# MC21R01_uC_Power.net
KiCad netlist of a schematic drawn in Altium Designer
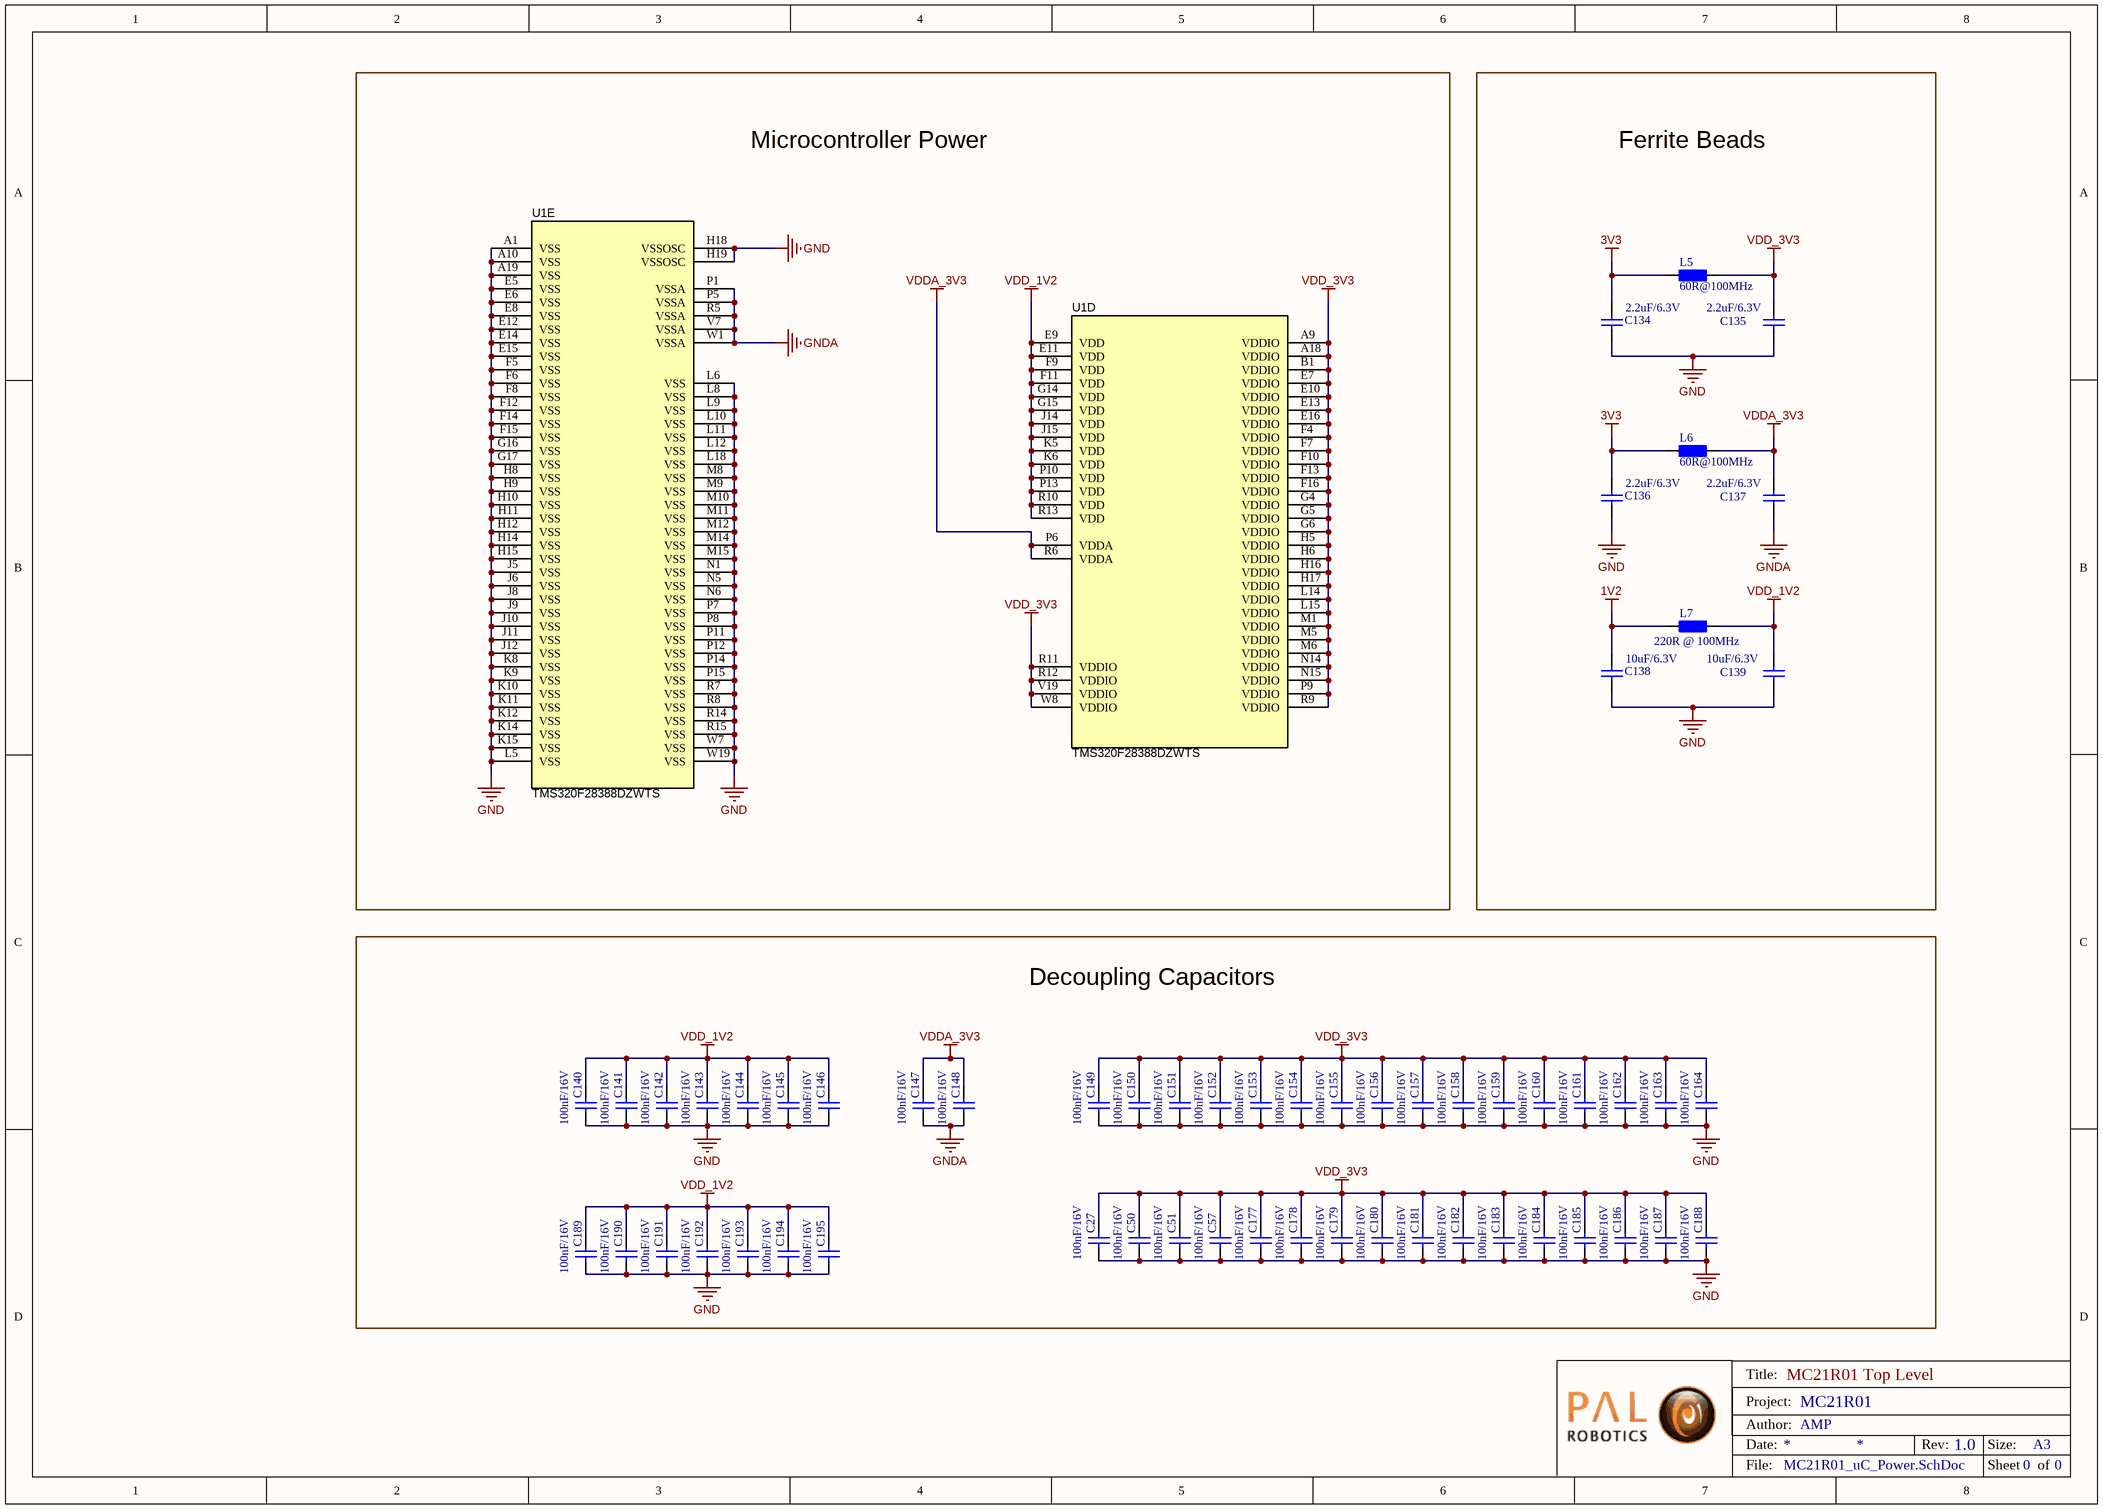
[diagram p0: MC21R01_uC_Power.SchDoc]

(export (version "E")
  (design (tool "Eeschema 10.0.6"))
  (components
    (comp (ref "C27")
      (value "100nF/16V")
      (footprint "PAL_Capacitors:0402 SMD Capacitor")
      (description "100nF/16V 0402 10% Tolerance X7R Multilayer Ceramic Chip Capacitor")
      (fields (field (name "Comment") "100nF/16V 0402 10% X7R"))
      (libsource (lib "PAL_Capacitors") (part "100nF/16V 0402 10% X7R"))
    )
    (comp (ref "C50")
      (value "100nF/16V")
      (footprint "PAL_Capacitors:0402 SMD Capacitor")
      (description "100nF/16V 0402 10% Tolerance X7R Multilayer Ceramic Chip Capacitor")
      (fields (field (name "Comment") "100nF/16V 0402 10% X7R"))
      (libsource (lib "PAL_Capacitors") (part "100nF/16V 0402 10% X7R"))
    )
    (comp (ref "C51")
      (value "100nF/16V")
      (footprint "PAL_Capacitors:0402 SMD Capacitor")
      (description "100nF/16V 0402 10% Tolerance X7R Multilayer Ceramic Chip Capacitor")
      (fields (field (name "Comment") "100nF/16V 0402 10% X7R"))
      (libsource (lib "PAL_Capacitors") (part "100nF/16V 0402 10% X7R"))
    )
    (comp (ref "C57")
      (value "100nF/16V")
      (footprint "PAL_Capacitors:0402 SMD Capacitor")
      (description "100nF/16V 0402 10% Tolerance X7R Multilayer Ceramic Chip Capacitor")
      (fields (field (name "Comment") "100nF/16V 0402 10% X7R"))
      (libsource (lib "PAL_Capacitors") (part "100nF/16V 0402 10% X7R"))
    )
    (comp (ref "C134")
      (value "2.2uF/6.3V")
      (footprint "PAL_Capacitors:0402 SMD Capacitor")
      (description "2.2uF/6.3V 0402 10% Tolerance X5R Multilayer Ceramic Chip Capacitor")
      (fields (field (name "Comment") "2.2uF/6.3V 0402 10% X5R"))
      (libsource (lib "PAL_Capacitors") (part "2.2uF/6.3V 0402 10% X5R_1"))
    )
    (comp (ref "C135")
      (value "2.2uF/6.3V")
      (footprint "PAL_Capacitors:0402 SMD Capacitor")
      (description "2.2uF/6.3V 0402 10% Tolerance X5R Multilayer Ceramic Chip Capacitor")
      (fields (field (name "Comment") "2.2uF/6.3V 0402 10% X5R"))
      (libsource (lib "PAL_Capacitors") (part "2.2uF/6.3V 0402 10% X5R_1"))
    )
    (comp (ref "C136")
      (value "2.2uF/6.3V")
      (footprint "PAL_Capacitors:0402 SMD Capacitor")
      (description "2.2uF/6.3V 0402 10% Tolerance X5R Multilayer Ceramic Chip Capacitor")
      (fields (field (name "Comment") "2.2uF/6.3V 0402 10% X5R"))
      (libsource (lib "PAL_Capacitors") (part "2.2uF/6.3V 0402 10% X5R_1"))
    )
    (comp (ref "C137")
      (value "2.2uF/6.3V")
      (footprint "PAL_Capacitors:0402 SMD Capacitor")
      (description "2.2uF/6.3V 0402 10% Tolerance X5R Multilayer Ceramic Chip Capacitor")
      (fields (field (name "Comment") "2.2uF/6.3V 0402 10% X5R"))
      (libsource (lib "PAL_Capacitors") (part "2.2uF/6.3V 0402 10% X5R_1"))
    )
    (comp (ref "C138")
      (value "10uF/6.3V")
      (footprint "PAL_Capacitors:0402 SMD Capacitor")
      (description "10uF/6.3V 0402 20% Tolerance X5R Multilayer Ceramic Chip Capacitor")
      (fields (field (name "Comment") "10uF/6.3V 0402 20% X5R"))
      (libsource (lib "PAL_Capacitors") (part "10uF/6.3V 0402 20% X5R"))
    )
    (comp (ref "C139")
      (value "10uF/6.3V")
      (footprint "PAL_Capacitors:0402 SMD Capacitor")
      (description "10uF/6.3V 0402 20% Tolerance X5R Multilayer Ceramic Chip Capacitor")
      (fields (field (name "Comment") "10uF/6.3V 0402 20% X5R"))
      (libsource (lib "PAL_Capacitors") (part "10uF/6.3V 0402 20% X5R"))
    )
    (comp (ref "C140")
      (value "100nF/16V")
      (footprint "PAL_Capacitors:0402 SMD Capacitor")
      (description "100nF/16V 0402 10% Tolerance X7R Multilayer Ceramic Chip Capacitor")
      (fields (field (name "Comment") "100nF/16V 0402 10% X7R"))
      (libsource (lib "PAL_Capacitors") (part "100nF/16V 0402 10% X7R"))
    )
    (comp (ref "C141")
      (value "100nF/16V")
      (footprint "PAL_Capacitors:0402 SMD Capacitor")
      (description "100nF/16V 0402 10% Tolerance X7R Multilayer Ceramic Chip Capacitor")
      (fields (field (name "Comment") "100nF/16V 0402 10% X7R"))
      (libsource (lib "PAL_Capacitors") (part "100nF/16V 0402 10% X7R"))
    )
    (comp (ref "C142")
      (value "100nF/16V")
      (footprint "PAL_Capacitors:0402 SMD Capacitor")
      (description "100nF/16V 0402 10% Tolerance X7R Multilayer Ceramic Chip Capacitor")
      (fields (field (name "Comment") "100nF/16V 0402 10% X7R"))
      (libsource (lib "PAL_Capacitors") (part "100nF/16V 0402 10% X7R"))
    )
    (comp (ref "C143")
      (value "100nF/16V")
      (footprint "PAL_Capacitors:0402 SMD Capacitor")
      (description "100nF/16V 0402 10% Tolerance X7R Multilayer Ceramic Chip Capacitor")
      (fields (field (name "Comment") "100nF/16V 0402 10% X7R"))
      (libsource (lib "PAL_Capacitors") (part "100nF/16V 0402 10% X7R"))
    )
    (comp (ref "C144")
      (value "100nF/16V")
      (footprint "PAL_Capacitors:0402 SMD Capacitor")
      (description "100nF/16V 0402 10% Tolerance X7R Multilayer Ceramic Chip Capacitor")
      (fields (field (name "Comment") "100nF/16V 0402 10% X7R"))
      (libsource (lib "PAL_Capacitors") (part "100nF/16V 0402 10% X7R"))
    )
    (comp (ref "C145")
      (value "100nF/16V")
      (footprint "PAL_Capacitors:0402 SMD Capacitor")
      (description "100nF/16V 0402 10% Tolerance X7R Multilayer Ceramic Chip Capacitor")
      (fields (field (name "Comment") "100nF/16V 0402 10% X7R"))
      (libsource (lib "PAL_Capacitors") (part "100nF/16V 0402 10% X7R"))
    )
    (comp (ref "C146")
      (value "100nF/16V")
      (footprint "PAL_Capacitors:0402 SMD Capacitor")
      (description "100nF/16V 0402 10% Tolerance X7R Multilayer Ceramic Chip Capacitor")
      (fields (field (name "Comment") "100nF/16V 0402 10% X7R"))
      (libsource (lib "PAL_Capacitors") (part "100nF/16V 0402 10% X7R"))
    )
    (comp (ref "C147")
      (value "100nF/16V")
      (footprint "PAL_Capacitors:0402 SMD Capacitor")
      (description "100nF/16V 0402 10% Tolerance X7R Multilayer Ceramic Chip Capacitor")
      (fields (field (name "Comment") "100nF/16V 0402 10% X7R"))
      (libsource (lib "PAL_Capacitors") (part "100nF/16V 0402 10% X7R"))
    )
    (comp (ref "C148")
      (value "100nF/16V")
      (footprint "PAL_Capacitors:0402 SMD Capacitor")
      (description "100nF/16V 0402 10% Tolerance X7R Multilayer Ceramic Chip Capacitor")
      (fields (field (name "Comment") "100nF/16V 0402 10% X7R"))
      (libsource (lib "PAL_Capacitors") (part "100nF/16V 0402 10% X7R"))
    )
    (comp (ref "C149")
      (value "100nF/16V")
      (footprint "PAL_Capacitors:0402 SMD Capacitor")
      (description "100nF/16V 0402 10% Tolerance X7R Multilayer Ceramic Chip Capacitor")
      (fields (field (name "Comment") "100nF/16V 0402 10% X7R"))
      (libsource (lib "PAL_Capacitors") (part "100nF/16V 0402 10% X7R"))
    )
    (comp (ref "C150")
      (value "100nF/16V")
      (footprint "PAL_Capacitors:0402 SMD Capacitor")
      (description "100nF/16V 0402 10% Tolerance X7R Multilayer Ceramic Chip Capacitor")
      (fields (field (name "Comment") "100nF/16V 0402 10% X7R"))
      (libsource (lib "PAL_Capacitors") (part "100nF/16V 0402 10% X7R"))
    )
    (comp (ref "C151")
      (value "100nF/16V")
      (footprint "PAL_Capacitors:0402 SMD Capacitor")
      (description "100nF/16V 0402 10% Tolerance X7R Multilayer Ceramic Chip Capacitor")
      (fields (field (name "Comment") "100nF/16V 0402 10% X7R"))
      (libsource (lib "PAL_Capacitors") (part "100nF/16V 0402 10% X7R"))
    )
    (comp (ref "C152")
      (value "100nF/16V")
      (footprint "PAL_Capacitors:0402 SMD Capacitor")
      (description "100nF/16V 0402 10% Tolerance X7R Multilayer Ceramic Chip Capacitor")
      (fields (field (name "Comment") "100nF/16V 0402 10% X7R"))
      (libsource (lib "PAL_Capacitors") (part "100nF/16V 0402 10% X7R"))
    )
    (comp (ref "C153")
      (value "100nF/16V")
      (footprint "PAL_Capacitors:0402 SMD Capacitor")
      (description "100nF/16V 0402 10% Tolerance X7R Multilayer Ceramic Chip Capacitor")
      (fields (field (name "Comment") "100nF/16V 0402 10% X7R"))
      (libsource (lib "PAL_Capacitors") (part "100nF/16V 0402 10% X7R"))
    )
    (comp (ref "C154")
      (value "100nF/16V")
      (footprint "PAL_Capacitors:0402 SMD Capacitor")
      (description "100nF/16V 0402 10% Tolerance X7R Multilayer Ceramic Chip Capacitor")
      (fields (field (name "Comment") "100nF/16V 0402 10% X7R"))
      (libsource (lib "PAL_Capacitors") (part "100nF/16V 0402 10% X7R"))
    )
    (comp (ref "C155")
      (value "100nF/16V")
      (footprint "PAL_Capacitors:0402 SMD Capacitor")
      (description "100nF/16V 0402 10% Tolerance X7R Multilayer Ceramic Chip Capacitor")
      (fields (field (name "Comment") "100nF/16V 0402 10% X7R"))
      (libsource (lib "PAL_Capacitors") (part "100nF/16V 0402 10% X7R"))
    )
    (comp (ref "C156")
      (value "100nF/16V")
      (footprint "PAL_Capacitors:0402 SMD Capacitor")
      (description "100nF/16V 0402 10% Tolerance X7R Multilayer Ceramic Chip Capacitor")
      (fields (field (name "Comment") "100nF/16V 0402 10% X7R"))
      (libsource (lib "PAL_Capacitors") (part "100nF/16V 0402 10% X7R"))
    )
    (comp (ref "C157")
      (value "100nF/16V")
      (footprint "PAL_Capacitors:0402 SMD Capacitor")
      (description "100nF/16V 0402 10% Tolerance X7R Multilayer Ceramic Chip Capacitor")
      (fields (field (name "Comment") "100nF/16V 0402 10% X7R"))
      (libsource (lib "PAL_Capacitors") (part "100nF/16V 0402 10% X7R"))
    )
    (comp (ref "C158")
      (value "100nF/16V")
      (footprint "PAL_Capacitors:0402 SMD Capacitor")
      (description "100nF/16V 0402 10% Tolerance X7R Multilayer Ceramic Chip Capacitor")
      (fields (field (name "Comment") "100nF/16V 0402 10% X7R"))
      (libsource (lib "PAL_Capacitors") (part "100nF/16V 0402 10% X7R"))
    )
    (comp (ref "C159")
      (value "100nF/16V")
      (footprint "PAL_Capacitors:0402 SMD Capacitor")
      (description "100nF/16V 0402 10% Tolerance X7R Multilayer Ceramic Chip Capacitor")
      (fields (field (name "Comment") "100nF/16V 0402 10% X7R"))
      (libsource (lib "PAL_Capacitors") (part "100nF/16V 0402 10% X7R"))
    )
    (comp (ref "C160")
      (value "100nF/16V")
      (footprint "PAL_Capacitors:0402 SMD Capacitor")
      (description "100nF/16V 0402 10% Tolerance X7R Multilayer Ceramic Chip Capacitor")
      (fields (field (name "Comment") "100nF/16V 0402 10% X7R"))
      (libsource (lib "PAL_Capacitors") (part "100nF/16V 0402 10% X7R"))
    )
    (comp (ref "C161")
      (value "100nF/16V")
      (footprint "PAL_Capacitors:0402 SMD Capacitor")
      (description "100nF/16V 0402 10% Tolerance X7R Multilayer Ceramic Chip Capacitor")
      (fields (field (name "Comment") "100nF/16V 0402 10% X7R"))
      (libsource (lib "PAL_Capacitors") (part "100nF/16V 0402 10% X7R"))
    )
    (comp (ref "C162")
      (value "100nF/16V")
      (footprint "PAL_Capacitors:0402 SMD Capacitor")
      (description "100nF/16V 0402 10% Tolerance X7R Multilayer Ceramic Chip Capacitor")
      (fields (field (name "Comment") "100nF/16V 0402 10% X7R"))
      (libsource (lib "PAL_Capacitors") (part "100nF/16V 0402 10% X7R"))
    )
    (comp (ref "C163")
      (value "100nF/16V")
      (footprint "PAL_Capacitors:0402 SMD Capacitor")
      (description "100nF/16V 0402 10% Tolerance X7R Multilayer Ceramic Chip Capacitor")
      (fields (field (name "Comment") "100nF/16V 0402 10% X7R"))
      (libsource (lib "PAL_Capacitors") (part "100nF/16V 0402 10% X7R"))
    )
    (comp (ref "C164")
      (value "100nF/16V")
      (footprint "PAL_Capacitors:0402 SMD Capacitor")
      (description "100nF/16V 0402 10% Tolerance X7R Multilayer Ceramic Chip Capacitor")
      (fields (field (name "Comment") "100nF/16V 0402 10% X7R"))
      (libsource (lib "PAL_Capacitors") (part "100nF/16V 0402 10% X7R"))
    )
    (comp (ref "C177")
      (value "100nF/16V")
      (footprint "PAL_Capacitors:0402 SMD Capacitor")
      (description "100nF/16V 0402 10% Tolerance X7R Multilayer Ceramic Chip Capacitor")
      (fields (field (name "Comment") "100nF/16V 0402 10% X7R"))
      (libsource (lib "PAL_Capacitors") (part "100nF/16V 0402 10% X7R"))
    )
    (comp (ref "C178")
      (value "100nF/16V")
      (footprint "PAL_Capacitors:0402 SMD Capacitor")
      (description "100nF/16V 0402 10% Tolerance X7R Multilayer Ceramic Chip Capacitor")
      (fields (field (name "Comment") "100nF/16V 0402 10% X7R"))
      (libsource (lib "PAL_Capacitors") (part "100nF/16V 0402 10% X7R"))
    )
    (comp (ref "C179")
      (value "100nF/16V")
      (footprint "PAL_Capacitors:0402 SMD Capacitor")
      (description "100nF/16V 0402 10% Tolerance X7R Multilayer Ceramic Chip Capacitor")
      (fields (field (name "Comment") "100nF/16V 0402 10% X7R"))
      (libsource (lib "PAL_Capacitors") (part "100nF/16V 0402 10% X7R"))
    )
    (comp (ref "C180")
      (value "100nF/16V")
      (footprint "PAL_Capacitors:0402 SMD Capacitor")
      (description "100nF/16V 0402 10% Tolerance X7R Multilayer Ceramic Chip Capacitor")
      (fields (field (name "Comment") "100nF/16V 0402 10% X7R"))
      (libsource (lib "PAL_Capacitors") (part "100nF/16V 0402 10% X7R"))
    )
    (comp (ref "C181")
      (value "100nF/16V")
      (footprint "PAL_Capacitors:0402 SMD Capacitor")
      (description "100nF/16V 0402 10% Tolerance X7R Multilayer Ceramic Chip Capacitor")
      (fields (field (name "Comment") "100nF/16V 0402 10% X7R"))
      (libsource (lib "PAL_Capacitors") (part "100nF/16V 0402 10% X7R"))
    )
    (comp (ref "C182")
      (value "100nF/16V")
      (footprint "PAL_Capacitors:0402 SMD Capacitor")
      (description "100nF/16V 0402 10% Tolerance X7R Multilayer Ceramic Chip Capacitor")
      (fields (field (name "Comment") "100nF/16V 0402 10% X7R"))
      (libsource (lib "PAL_Capacitors") (part "100nF/16V 0402 10% X7R"))
    )
    (comp (ref "C183")
      (value "100nF/16V")
      (footprint "PAL_Capacitors:0402 SMD Capacitor")
      (description "100nF/16V 0402 10% Tolerance X7R Multilayer Ceramic Chip Capacitor")
      (fields (field (name "Comment") "100nF/16V 0402 10% X7R"))
      (libsource (lib "PAL_Capacitors") (part "100nF/16V 0402 10% X7R"))
    )
    (comp (ref "C184")
      (value "100nF/16V")
      (footprint "PAL_Capacitors:0402 SMD Capacitor")
      (description "100nF/16V 0402 10% Tolerance X7R Multilayer Ceramic Chip Capacitor")
      (fields (field (name "Comment") "100nF/16V 0402 10% X7R"))
      (libsource (lib "PAL_Capacitors") (part "100nF/16V 0402 10% X7R"))
    )
    (comp (ref "C185")
      (value "100nF/16V")
      (footprint "PAL_Capacitors:0402 SMD Capacitor")
      (description "100nF/16V 0402 10% Tolerance X7R Multilayer Ceramic Chip Capacitor")
      (fields (field (name "Comment") "100nF/16V 0402 10% X7R"))
      (libsource (lib "PAL_Capacitors") (part "100nF/16V 0402 10% X7R"))
    )
    (comp (ref "C186")
      (value "100nF/16V")
      (footprint "PAL_Capacitors:0402 SMD Capacitor")
      (description "100nF/16V 0402 10% Tolerance X7R Multilayer Ceramic Chip Capacitor")
      (fields (field (name "Comment") "100nF/16V 0402 10% X7R"))
      (libsource (lib "PAL_Capacitors") (part "100nF/16V 0402 10% X7R"))
    )
    (comp (ref "C187")
      (value "100nF/16V")
      (footprint "PAL_Capacitors:0402 SMD Capacitor")
      (description "100nF/16V 0402 10% Tolerance X7R Multilayer Ceramic Chip Capacitor")
      (fields (field (name "Comment") "100nF/16V 0402 10% X7R"))
      (libsource (lib "PAL_Capacitors") (part "100nF/16V 0402 10% X7R"))
    )
    (comp (ref "C188")
      (value "100nF/16V")
      (footprint "PAL_Capacitors:0402 SMD Capacitor")
      (description "100nF/16V 0402 10% Tolerance X7R Multilayer Ceramic Chip Capacitor")
      (fields (field (name "Comment") "100nF/16V 0402 10% X7R"))
      (libsource (lib "PAL_Capacitors") (part "100nF/16V 0402 10% X7R"))
    )
    (comp (ref "C189")
      (value "100nF/16V")
      (footprint "PAL_Capacitors:0402 SMD Capacitor")
      (description "100nF/16V 0402 10% Tolerance X7R Multilayer Ceramic Chip Capacitor")
      (fields (field (name "Comment") "100nF/16V 0402 10% X7R"))
      (libsource (lib "PAL_Capacitors") (part "100nF/16V 0402 10% X7R"))
    )
    (comp (ref "C190")
      (value "100nF/16V")
      (footprint "PAL_Capacitors:0402 SMD Capacitor")
      (description "100nF/16V 0402 10% Tolerance X7R Multilayer Ceramic Chip Capacitor")
      (fields (field (name "Comment") "100nF/16V 0402 10% X7R"))
      (libsource (lib "PAL_Capacitors") (part "100nF/16V 0402 10% X7R"))
    )
    (comp (ref "C191")
      (value "100nF/16V")
      (footprint "PAL_Capacitors:0402 SMD Capacitor")
      (description "100nF/16V 0402 10% Tolerance X7R Multilayer Ceramic Chip Capacitor")
      (fields (field (name "Comment") "100nF/16V 0402 10% X7R"))
      (libsource (lib "PAL_Capacitors") (part "100nF/16V 0402 10% X7R"))
    )
    (comp (ref "C192")
      (value "100nF/16V")
      (footprint "PAL_Capacitors:0402 SMD Capacitor")
      (description "100nF/16V 0402 10% Tolerance X7R Multilayer Ceramic Chip Capacitor")
      (fields (field (name "Comment") "100nF/16V 0402 10% X7R"))
      (libsource (lib "PAL_Capacitors") (part "100nF/16V 0402 10% X7R"))
    )
    (comp (ref "C193")
      (value "100nF/16V")
      (footprint "PAL_Capacitors:0402 SMD Capacitor")
      (description "100nF/16V 0402 10% Tolerance X7R Multilayer Ceramic Chip Capacitor")
      (fields (field (name "Comment") "100nF/16V 0402 10% X7R"))
      (libsource (lib "PAL_Capacitors") (part "100nF/16V 0402 10% X7R"))
    )
    (comp (ref "C194")
      (value "100nF/16V")
      (footprint "PAL_Capacitors:0402 SMD Capacitor")
      (description "100nF/16V 0402 10% Tolerance X7R Multilayer Ceramic Chip Capacitor")
      (fields (field (name "Comment") "100nF/16V 0402 10% X7R"))
      (libsource (lib "PAL_Capacitors") (part "100nF/16V 0402 10% X7R"))
    )
    (comp (ref "C195")
      (value "100nF/16V")
      (footprint "PAL_Capacitors:0402 SMD Capacitor")
      (description "100nF/16V 0402 10% Tolerance X7R Multilayer Ceramic Chip Capacitor")
      (fields (field (name "Comment") "100nF/16V 0402 10% X7R"))
      (libsource (lib "PAL_Capacitors") (part "100nF/16V 0402 10% X7R"))
    )
    (comp (ref "L5")
      (value "60R@100MHz")
      (footprint "PAL_Inductors:0603 SMD inductor")
      (description "Ferrite Bead, 60 ohm, 0603 [1608 Metric], 3 A, 0.04 ohm, ± 25%")
      (fields (field (name "MPN") "742792602") (field (name "MF") "Wurth Electronik"))
      (libsource (lib "PAL_Inductors") (part "FB, 60 ohm, 0603 [1608 Metric], 3 A, 0.04 ohm, ± 25%"))
    )
    (comp (ref "L6")
      (value "60R@100MHz")
      (footprint "PAL_Inductors:0603 SMD inductor")
      (description "Ferrite Bead, 60 ohm, 0603 [1608 Metric], 3 A, 0.04 ohm, ± 25%")
      (fields (field (name "MPN") "742792602") (field (name "MF") "Wurth Electronik"))
      (libsource (lib "PAL_Inductors") (part "FB, 60 ohm, 0603 [1608 Metric], 3 A, 0.04 ohm, ± 25%"))
    )
    (comp (ref "L7")
      (value "220R @ 100MHz")
      (footprint "PAL_Inductors:0603 SMD inductor")
      (description "Ferrite Bead, 220 ohm, 0603 [1608 Metric], 2 A, 0.05 ohm, ± 25%")
      (fields (field (name "MPN") "BLM18EG221SN1D") (field (name "MF") "MURATA"))
      (libsource (lib "PAL_Inductors") (part "FB, 220 ohm, 0603 [1608 Metric], 2 A, 0.05 ohm, ± 25%"))
    )
    (comp (ref "U1")
      (value "TMS320F28388DZWTS")
      (footprint "ZWT0337A")
      (description "TMS320F28388DZWTS, ZWT0337A (NFBGA-337)")
      (fields
        (field (name "MANUFACTURER") "Texas Instruments")
        (field (name "PARTNUMBER") "TMS320F28388DZWTS")
      )
      (libsource (lib "PAL_devices") (part "TMS320F28388"))
    )
  )
  (nets
    (net (code "1") (name "1V2") (class "Default")
      (node (ref "C138") (pin "1") (pinfunction "1_1") (pintype "passive"))
      (node (ref "L7") (pin "2") (pinfunction "2_2") (pintype "passive"))
    )
    (net (code "2") (name "3V3") (class "Default")
      (node (ref "C134") (pin "1") (pinfunction "1_1") (pintype "passive"))
      (node (ref "C136") (pin "1") (pinfunction "1_1") (pintype "passive"))
      (node (ref "L5") (pin "2") (pinfunction "2_2") (pintype "passive"))
      (node (ref "L6") (pin "2") (pinfunction "2_2") (pintype "passive"))
    )
    (net (code "3") (name "GND") (class "Default")
      (node (ref "C134") (pin "2") (pinfunction "2_2") (pintype "passive"))
      (node (ref "C135") (pin "2") (pinfunction "2_2") (pintype "passive"))
      (node (ref "C136") (pin "2") (pinfunction "2_2") (pintype "passive"))
      (node (ref "C138") (pin "2") (pinfunction "2_2") (pintype "passive"))
      (node (ref "C139") (pin "2") (pinfunction "2_2") (pintype "passive"))
      (node (ref "C140") (pin "2") (pinfunction "2_2") (pintype "passive"))
      (node (ref "C141") (pin "2") (pinfunction "2_2") (pintype "passive"))
      (node (ref "C142") (pin "2") (pinfunction "2_2") (pintype "passive"))
      (node (ref "C143") (pin "2") (pinfunction "2_2") (pintype "passive"))
      (node (ref "C144") (pin "2") (pinfunction "2_2") (pintype "passive"))
      (node (ref "C145") (pin "2") (pinfunction "2_2") (pintype "passive"))
      (node (ref "C146") (pin "2") (pinfunction "2_2") (pintype "passive"))
      (node (ref "C149") (pin "2") (pinfunction "2_2") (pintype "passive"))
      (node (ref "C150") (pin "2") (pinfunction "2_2") (pintype "passive"))
      (node (ref "C151") (pin "2") (pinfunction "2_2") (pintype "passive"))
      (node (ref "C152") (pin "2") (pinfunction "2_2") (pintype "passive"))
      (node (ref "C153") (pin "2") (pinfunction "2_2") (pintype "passive"))
      (node (ref "C154") (pin "2") (pinfunction "2_2") (pintype "passive"))
      (node (ref "C155") (pin "2") (pinfunction "2_2") (pintype "passive"))
      (node (ref "C156") (pin "2") (pinfunction "2_2") (pintype "passive"))
      (node (ref "C157") (pin "2") (pinfunction "2_2") (pintype "passive"))
      (node (ref "C158") (pin "2") (pinfunction "2_2") (pintype "passive"))
      (node (ref "C159") (pin "2") (pinfunction "2_2") (pintype "passive"))
      (node (ref "C160") (pin "2") (pinfunction "2_2") (pintype "passive"))
      (node (ref "C161") (pin "2") (pinfunction "2_2") (pintype "passive"))
      (node (ref "C162") (pin "2") (pinfunction "2_2") (pintype "passive"))
      (node (ref "C163") (pin "2") (pinfunction "2_2") (pintype "passive"))
      (node (ref "C164") (pin "2") (pinfunction "2_2") (pintype "passive"))
      (node (ref "C177") (pin "2") (pinfunction "2_2") (pintype "passive"))
      (node (ref "C178") (pin "2") (pinfunction "2_2") (pintype "passive"))
      (node (ref "C179") (pin "2") (pinfunction "2_2") (pintype "passive"))
      (node (ref "C180") (pin "2") (pinfunction "2_2") (pintype "passive"))
      (node (ref "C181") (pin "2") (pinfunction "2_2") (pintype "passive"))
      (node (ref "C182") (pin "2") (pinfunction "2_2") (pintype "passive"))
      (node (ref "C183") (pin "2") (pinfunction "2_2") (pintype "passive"))
      (node (ref "C184") (pin "2") (pinfunction "2_2") (pintype "passive"))
      (node (ref "C185") (pin "2") (pinfunction "2_2") (pintype "passive"))
      (node (ref "C186") (pin "2") (pinfunction "2_2") (pintype "passive"))
      (node (ref "C187") (pin "2") (pinfunction "2_2") (pintype "passive"))
      (node (ref "C188") (pin "2") (pinfunction "2_2") (pintype "passive"))
      (node (ref "C189") (pin "2") (pinfunction "2_2") (pintype "passive"))
      (node (ref "C190") (pin "2") (pinfunction "2_2") (pintype "passive"))
      (node (ref "C191") (pin "2") (pinfunction "2_2") (pintype "passive"))
      (node (ref "C192") (pin "2") (pinfunction "2_2") (pintype "passive"))
      (node (ref "C193") (pin "2") (pinfunction "2_2") (pintype "passive"))
      (node (ref "C194") (pin "2") (pinfunction "2_2") (pintype "passive"))
      (node (ref "C195") (pin "2") (pinfunction "2_2") (pintype "passive"))
      (node (ref "C27") (pin "2") (pinfunction "2_2") (pintype "passive"))
      (node (ref "C50") (pin "2") (pinfunction "2_2") (pintype "passive"))
      (node (ref "C51") (pin "2") (pinfunction "2_2") (pintype "passive"))
      (node (ref "C57") (pin "2") (pinfunction "2_2") (pintype "passive"))
      (node (ref "U1") (pin "A1") (pinfunction "VSS_A1") (pintype "power_in"))
      (node (ref "U1") (pin "A10") (pinfunction "VSS_A10") (pintype "power_in"))
      (node (ref "U1") (pin "A19") (pinfunction "VSS_A19") (pintype "power_in"))
      (node (ref "U1") (pin "E12") (pinfunction "VSS_E12") (pintype "power_in"))
      (node (ref "U1") (pin "E14") (pinfunction "VSS_E14") (pintype "power_in"))
      (node (ref "U1") (pin "E15") (pinfunction "VSS_E15") (pintype "power_in"))
      (node (ref "U1") (pin "E5") (pinfunction "VSS_E5") (pintype "power_in"))
      (node (ref "U1") (pin "E6") (pinfunction "VSS_E6") (pintype "power_in"))
      (node (ref "U1") (pin "E8") (pinfunction "VSS_E8") (pintype "power_in"))
      (node (ref "U1") (pin "F12") (pinfunction "VSS_F12") (pintype "power_in"))
      (node (ref "U1") (pin "F14") (pinfunction "VSS_F14") (pintype "power_in"))
      (node (ref "U1") (pin "F15") (pinfunction "VSS_F15") (pintype "power_in"))
      (node (ref "U1") (pin "F5") (pinfunction "VSS_F5") (pintype "power_in"))
      (node (ref "U1") (pin "F6") (pinfunction "VSS_F6") (pintype "power_in"))
      (node (ref "U1") (pin "F8") (pinfunction "VSS_F8") (pintype "power_in"))
      (node (ref "U1") (pin "G16") (pinfunction "VSS_G16") (pintype "power_in"))
      (node (ref "U1") (pin "G17") (pinfunction "VSS_G17") (pintype "power_in"))
      (node (ref "U1") (pin "H10") (pinfunction "VSS_H10") (pintype "power_in"))
      (node (ref "U1") (pin "H11") (pinfunction "VSS_H11") (pintype "power_in"))
      (node (ref "U1") (pin "H12") (pinfunction "VSS_H12") (pintype "power_in"))
      (node (ref "U1") (pin "H14") (pinfunction "VSS_H14") (pintype "power_in"))
      (node (ref "U1") (pin "H15") (pinfunction "VSS_H15") (pintype "power_in"))
      (node (ref "U1") (pin "H18") (pinfunction "VSSOSC_H18") (pintype "power_in"))
      (node (ref "U1") (pin "H19") (pinfunction "VSSOSC_H19") (pintype "power_in"))
      (node (ref "U1") (pin "H8") (pinfunction "VSS_H8") (pintype "power_in"))
      (node (ref "U1") (pin "H9") (pinfunction "VSS_H9") (pintype "power_in"))
      (node (ref "U1") (pin "J10") (pinfunction "VSS_J10") (pintype "power_in"))
      (node (ref "U1") (pin "J11") (pinfunction "VSS_J11") (pintype "power_in"))
      (node (ref "U1") (pin "J12") (pinfunction "VSS_J12") (pintype "power_in"))
      (node (ref "U1") (pin "J5") (pinfunction "VSS_J5") (pintype "power_in"))
      (node (ref "U1") (pin "J6") (pinfunction "VSS_J6") (pintype "power_in"))
      (node (ref "U1") (pin "J8") (pinfunction "VSS_J8") (pintype "power_in"))
      (node (ref "U1") (pin "J9") (pinfunction "VSS_J9") (pintype "power_in"))
      (node (ref "U1") (pin "K10") (pinfunction "VSS_K10") (pintype "power_in"))
      (node (ref "U1") (pin "K11") (pinfunction "VSS_K11") (pintype "power_in"))
      (node (ref "U1") (pin "K12") (pinfunction "VSS_K12") (pintype "power_in"))
      (node (ref "U1") (pin "K14") (pinfunction "VSS_K14") (pintype "power_in"))
      (node (ref "U1") (pin "K15") (pinfunction "VSS_K15") (pintype "power_in"))
      (node (ref "U1") (pin "K8") (pinfunction "VSS_K8") (pintype "power_in"))
      (node (ref "U1") (pin "K9") (pinfunction "VSS_K9") (pintype "power_in"))
      (node (ref "U1") (pin "L10") (pinfunction "VSS_L10") (pintype "power_in"))
      (node (ref "U1") (pin "L11") (pinfunction "VSS_L11") (pintype "power_in"))
      (node (ref "U1") (pin "L12") (pinfunction "VSS_L12") (pintype "power_in"))
      (node (ref "U1") (pin "L18") (pinfunction "VSS_L18") (pintype "power_in"))
      (node (ref "U1") (pin "L5") (pinfunction "VSS_L5") (pintype "power_in"))
      (node (ref "U1") (pin "L6") (pinfunction "VSS_L6") (pintype "power_in"))
      (node (ref "U1") (pin "L8") (pinfunction "VSS_L8") (pintype "power_in"))
      (node (ref "U1") (pin "L9") (pinfunction "VSS_L9") (pintype "power_in"))
      (node (ref "U1") (pin "M10") (pinfunction "VSS_M10") (pintype "power_in"))
      (node (ref "U1") (pin "M11") (pinfunction "VSS_M11") (pintype "power_in"))
      (node (ref "U1") (pin "M12") (pinfunction "VSS_M12") (pintype "power_in"))
      (node (ref "U1") (pin "M14") (pinfunction "VSS_M14") (pintype "power_in"))
      (node (ref "U1") (pin "M15") (pinfunction "VSS_M15") (pintype "power_in"))
      (node (ref "U1") (pin "M8") (pinfunction "VSS_M8") (pintype "power_in"))
      (node (ref "U1") (pin "M9") (pinfunction "VSS_M9") (pintype "power_in"))
      (node (ref "U1") (pin "N1") (pinfunction "VSS_N1") (pintype "power_in"))
      (node (ref "U1") (pin "N5") (pinfunction "VSS_N5") (pintype "power_in"))
      (node (ref "U1") (pin "N6") (pinfunction "VSS_N6") (pintype "power_in"))
      (node (ref "U1") (pin "P11") (pinfunction "VSS_P11") (pintype "power_in"))
      (node (ref "U1") (pin "P12") (pinfunction "VSS_P12") (pintype "power_in"))
      (node (ref "U1") (pin "P14") (pinfunction "VSS_P14") (pintype "power_in"))
      (node (ref "U1") (pin "P15") (pinfunction "VSS_P15") (pintype "power_in"))
      (node (ref "U1") (pin "P7") (pinfunction "VSS_P7") (pintype "power_in"))
      (node (ref "U1") (pin "P8") (pinfunction "VSS_P8") (pintype "power_in"))
      (node (ref "U1") (pin "R14") (pinfunction "VSS_R14") (pintype "power_in"))
      (node (ref "U1") (pin "R15") (pinfunction "VSS_R15") (pintype "power_in"))
      (node (ref "U1") (pin "R7") (pinfunction "VSS_R7") (pintype "power_in"))
      (node (ref "U1") (pin "R8") (pinfunction "VSS_R8") (pintype "power_in"))
      (node (ref "U1") (pin "W19") (pinfunction "VSS_W19") (pintype "power_in"))
      (node (ref "U1") (pin "W7") (pinfunction "VSS_W7") (pintype "power_in"))
    )
    (net (code "4") (name "GNDA") (class "Default")
      (node (ref "C137") (pin "2") (pinfunction "2_2") (pintype "passive"))
      (node (ref "C147") (pin "2") (pinfunction "2_2") (pintype "passive"))
      (node (ref "C148") (pin "2") (pinfunction "2_2") (pintype "passive"))
      (node (ref "U1") (pin "P1") (pinfunction "VSSA_P1") (pintype "power_in"))
      (node (ref "U1") (pin "P5") (pinfunction "VSSA_P5") (pintype "power_in"))
      (node (ref "U1") (pin "R5") (pinfunction "VSSA_R5") (pintype "power_in"))
      (node (ref "U1") (pin "V7") (pinfunction "VSSA_V7") (pintype "power_in"))
      (node (ref "U1") (pin "W1") (pinfunction "VSSA_W1") (pintype "power_in"))
    )
    (net (code "5") (name "VDDA_3V3") (class "Default")
      (node (ref "C137") (pin "1") (pinfunction "1_1") (pintype "passive"))
      (node (ref "C147") (pin "1") (pinfunction "1_1") (pintype "passive"))
      (node (ref "C148") (pin "1") (pinfunction "1_1") (pintype "passive"))
      (node (ref "L6") (pin "1") (pinfunction "1_1") (pintype "passive"))
      (node (ref "U1") (pin "P6") (pinfunction "VDDA_P6") (pintype "power_in"))
      (node (ref "U1") (pin "R6") (pinfunction "VDDA_R6") (pintype "power_in"))
    )
    (net (code "6") (name "VDD_1V2") (class "Default")
      (node (ref "C139") (pin "1") (pinfunction "1_1") (pintype "passive"))
      (node (ref "C140") (pin "1") (pinfunction "1_1") (pintype "passive"))
      (node (ref "C141") (pin "1") (pinfunction "1_1") (pintype "passive"))
      (node (ref "C142") (pin "1") (pinfunction "1_1") (pintype "passive"))
      (node (ref "C143") (pin "1") (pinfunction "1_1") (pintype "passive"))
      (node (ref "C144") (pin "1") (pinfunction "1_1") (pintype "passive"))
      (node (ref "C145") (pin "1") (pinfunction "1_1") (pintype "passive"))
      (node (ref "C146") (pin "1") (pinfunction "1_1") (pintype "passive"))
      (node (ref "C189") (pin "1") (pinfunction "1_1") (pintype "passive"))
      (node (ref "C190") (pin "1") (pinfunction "1_1") (pintype "passive"))
      (node (ref "C191") (pin "1") (pinfunction "1_1") (pintype "passive"))
      (node (ref "C192") (pin "1") (pinfunction "1_1") (pintype "passive"))
      (node (ref "C193") (pin "1") (pinfunction "1_1") (pintype "passive"))
      (node (ref "C194") (pin "1") (pinfunction "1_1") (pintype "passive"))
      (node (ref "C195") (pin "1") (pinfunction "1_1") (pintype "passive"))
      (node (ref "L7") (pin "1") (pinfunction "1_1") (pintype "passive"))
      (node (ref "U1") (pin "E11") (pinfunction "VDD_E11") (pintype "power_in"))
      (node (ref "U1") (pin "E9") (pinfunction "VDD_E9") (pintype "power_in"))
      (node (ref "U1") (pin "F11") (pinfunction "VDD_F11") (pintype "power_in"))
      (node (ref "U1") (pin "F9") (pinfunction "VDD_F9") (pintype "power_in"))
      (node (ref "U1") (pin "G14") (pinfunction "VDD_G14") (pintype "power_in"))
      (node (ref "U1") (pin "G15") (pinfunction "VDD_G15") (pintype "power_in"))
      (node (ref "U1") (pin "J14") (pinfunction "VDD_J14") (pintype "power_in"))
      (node (ref "U1") (pin "J15") (pinfunction "VDD_J15") (pintype "power_in"))
      (node (ref "U1") (pin "K5") (pinfunction "VDD_K5") (pintype "power_in"))
      (node (ref "U1") (pin "K6") (pinfunction "VDD_K6") (pintype "power_in"))
      (node (ref "U1") (pin "P10") (pinfunction "VDD_P10") (pintype "power_in"))
      (node (ref "U1") (pin "P13") (pinfunction "VDD_P13") (pintype "power_in"))
      (node (ref "U1") (pin "R10") (pinfunction "VDD_R10") (pintype "power_in"))
      (node (ref "U1") (pin "R13") (pinfunction "VDD_R13") (pintype "power_in"))
    )
    (net (code "7") (name "VDD_3V3") (class "Default")
      (node (ref "C135") (pin "1") (pinfunction "1_1") (pintype "passive"))
      (node (ref "C149") (pin "1") (pinfunction "1_1") (pintype "passive"))
      (node (ref "C150") (pin "1") (pinfunction "1_1") (pintype "passive"))
      (node (ref "C151") (pin "1") (pinfunction "1_1") (pintype "passive"))
      (node (ref "C152") (pin "1") (pinfunction "1_1") (pintype "passive"))
      (node (ref "C153") (pin "1") (pinfunction "1_1") (pintype "passive"))
      (node (ref "C154") (pin "1") (pinfunction "1_1") (pintype "passive"))
      (node (ref "C155") (pin "1") (pinfunction "1_1") (pintype "passive"))
      (node (ref "C156") (pin "1") (pinfunction "1_1") (pintype "passive"))
      (node (ref "C157") (pin "1") (pinfunction "1_1") (pintype "passive"))
      (node (ref "C158") (pin "1") (pinfunction "1_1") (pintype "passive"))
      (node (ref "C159") (pin "1") (pinfunction "1_1") (pintype "passive"))
      (node (ref "C160") (pin "1") (pinfunction "1_1") (pintype "passive"))
      (node (ref "C161") (pin "1") (pinfunction "1_1") (pintype "passive"))
      (node (ref "C162") (pin "1") (pinfunction "1_1") (pintype "passive"))
      (node (ref "C163") (pin "1") (pinfunction "1_1") (pintype "passive"))
      (node (ref "C164") (pin "1") (pinfunction "1_1") (pintype "passive"))
      (node (ref "C177") (pin "1") (pinfunction "1_1") (pintype "passive"))
      (node (ref "C178") (pin "1") (pinfunction "1_1") (pintype "passive"))
      (node (ref "C179") (pin "1") (pinfunction "1_1") (pintype "passive"))
      (node (ref "C180") (pin "1") (pinfunction "1_1") (pintype "passive"))
      (node (ref "C181") (pin "1") (pinfunction "1_1") (pintype "passive"))
      (node (ref "C182") (pin "1") (pinfunction "1_1") (pintype "passive"))
      (node (ref "C183") (pin "1") (pinfunction "1_1") (pintype "passive"))
      (node (ref "C184") (pin "1") (pinfunction "1_1") (pintype "passive"))
      (node (ref "C185") (pin "1") (pinfunction "1_1") (pintype "passive"))
      (node (ref "C186") (pin "1") (pinfunction "1_1") (pintype "passive"))
      (node (ref "C187") (pin "1") (pinfunction "1_1") (pintype "passive"))
      (node (ref "C188") (pin "1") (pinfunction "1_1") (pintype "passive"))
      (node (ref "C27") (pin "1") (pinfunction "1_1") (pintype "passive"))
      (node (ref "C50") (pin "1") (pinfunction "1_1") (pintype "passive"))
      (node (ref "C51") (pin "1") (pinfunction "1_1") (pintype "passive"))
      (node (ref "C57") (pin "1") (pinfunction "1_1") (pintype "passive"))
      (node (ref "L5") (pin "1") (pinfunction "1_1") (pintype "passive"))
      (node (ref "U1") (pin "A18") (pinfunction "VDDIO_A18") (pintype "power_in"))
      (node (ref "U1") (pin "A9") (pinfunction "VDDIO_A9") (pintype "power_in"))
      (node (ref "U1") (pin "B1") (pinfunction "VDDIO_B1") (pintype "power_in"))
      (node (ref "U1") (pin "E10") (pinfunction "VDDIO_E10") (pintype "power_in"))
      (node (ref "U1") (pin "E13") (pinfunction "VDDIO_E13") (pintype "power_in"))
      (node (ref "U1") (pin "E16") (pinfunction "VDDIO_E16") (pintype "power_in"))
      (node (ref "U1") (pin "E7") (pinfunction "VDDIO_E7") (pintype "power_in"))
      (node (ref "U1") (pin "F10") (pinfunction "VDDIO_F10") (pintype "power_in"))
      (node (ref "U1") (pin "F13") (pinfunction "VDDIO_F13") (pintype "power_in"))
      (node (ref "U1") (pin "F16") (pinfunction "VDDIO_F16") (pintype "power_in"))
      (node (ref "U1") (pin "F4") (pinfunction "VDDIO_F4") (pintype "power_in"))
      (node (ref "U1") (pin "F7") (pinfunction "VDDIO_F7") (pintype "power_in"))
      (node (ref "U1") (pin "G4") (pinfunction "VDDIO_G4") (pintype "power_in"))
      (node (ref "U1") (pin "G5") (pinfunction "VDDIO_G5") (pintype "power_in"))
      (node (ref "U1") (pin "G6") (pinfunction "VDDIO_G6") (pintype "power_in"))
      (node (ref "U1") (pin "H16") (pinfunction "VDDIO_H16") (pintype "power_in"))
      (node (ref "U1") (pin "H17") (pinfunction "VDDIO_H17") (pintype "power_in"))
      (node (ref "U1") (pin "H5") (pinfunction "VDDIO_H5") (pintype "power_in"))
      (node (ref "U1") (pin "H6") (pinfunction "VDDIO_H6") (pintype "power_in"))
      (node (ref "U1") (pin "L14") (pinfunction "VDDIO_L14") (pintype "power_in"))
      (node (ref "U1") (pin "L15") (pinfunction "VDDIO_L15") (pintype "power_in"))
      (node (ref "U1") (pin "M1") (pinfunction "VDDIO_M1") (pintype "power_in"))
      (node (ref "U1") (pin "M5") (pinfunction "VDDIO_M5") (pintype "power_in"))
      (node (ref "U1") (pin "M6") (pinfunction "VDDIO_M6") (pintype "power_in"))
      (node (ref "U1") (pin "N14") (pinfunction "VDDIO_N14") (pintype "power_in"))
      (node (ref "U1") (pin "N15") (pinfunction "VDDIO_N15") (pintype "power_in"))
      (node (ref "U1") (pin "P9") (pinfunction "VDDIO_P9") (pintype "power_in"))
      (node (ref "U1") (pin "R11") (pinfunction "VDDIO_R11") (pintype "power_in"))
      (node (ref "U1") (pin "R12") (pinfunction "VDDIO_R12") (pintype "power_in"))
      (node (ref "U1") (pin "R9") (pinfunction "VDDIO_R9") (pintype "power_in"))
      (node (ref "U1") (pin "V19") (pinfunction "VDDIO_V19") (pintype "power_in"))
      (node (ref "U1") (pin "W8") (pinfunction "VDDIO_W8") (pintype "power_in"))
    )
  )
)
